# test_module.net
KiCad netlist of a schematic drawn in EAGLE
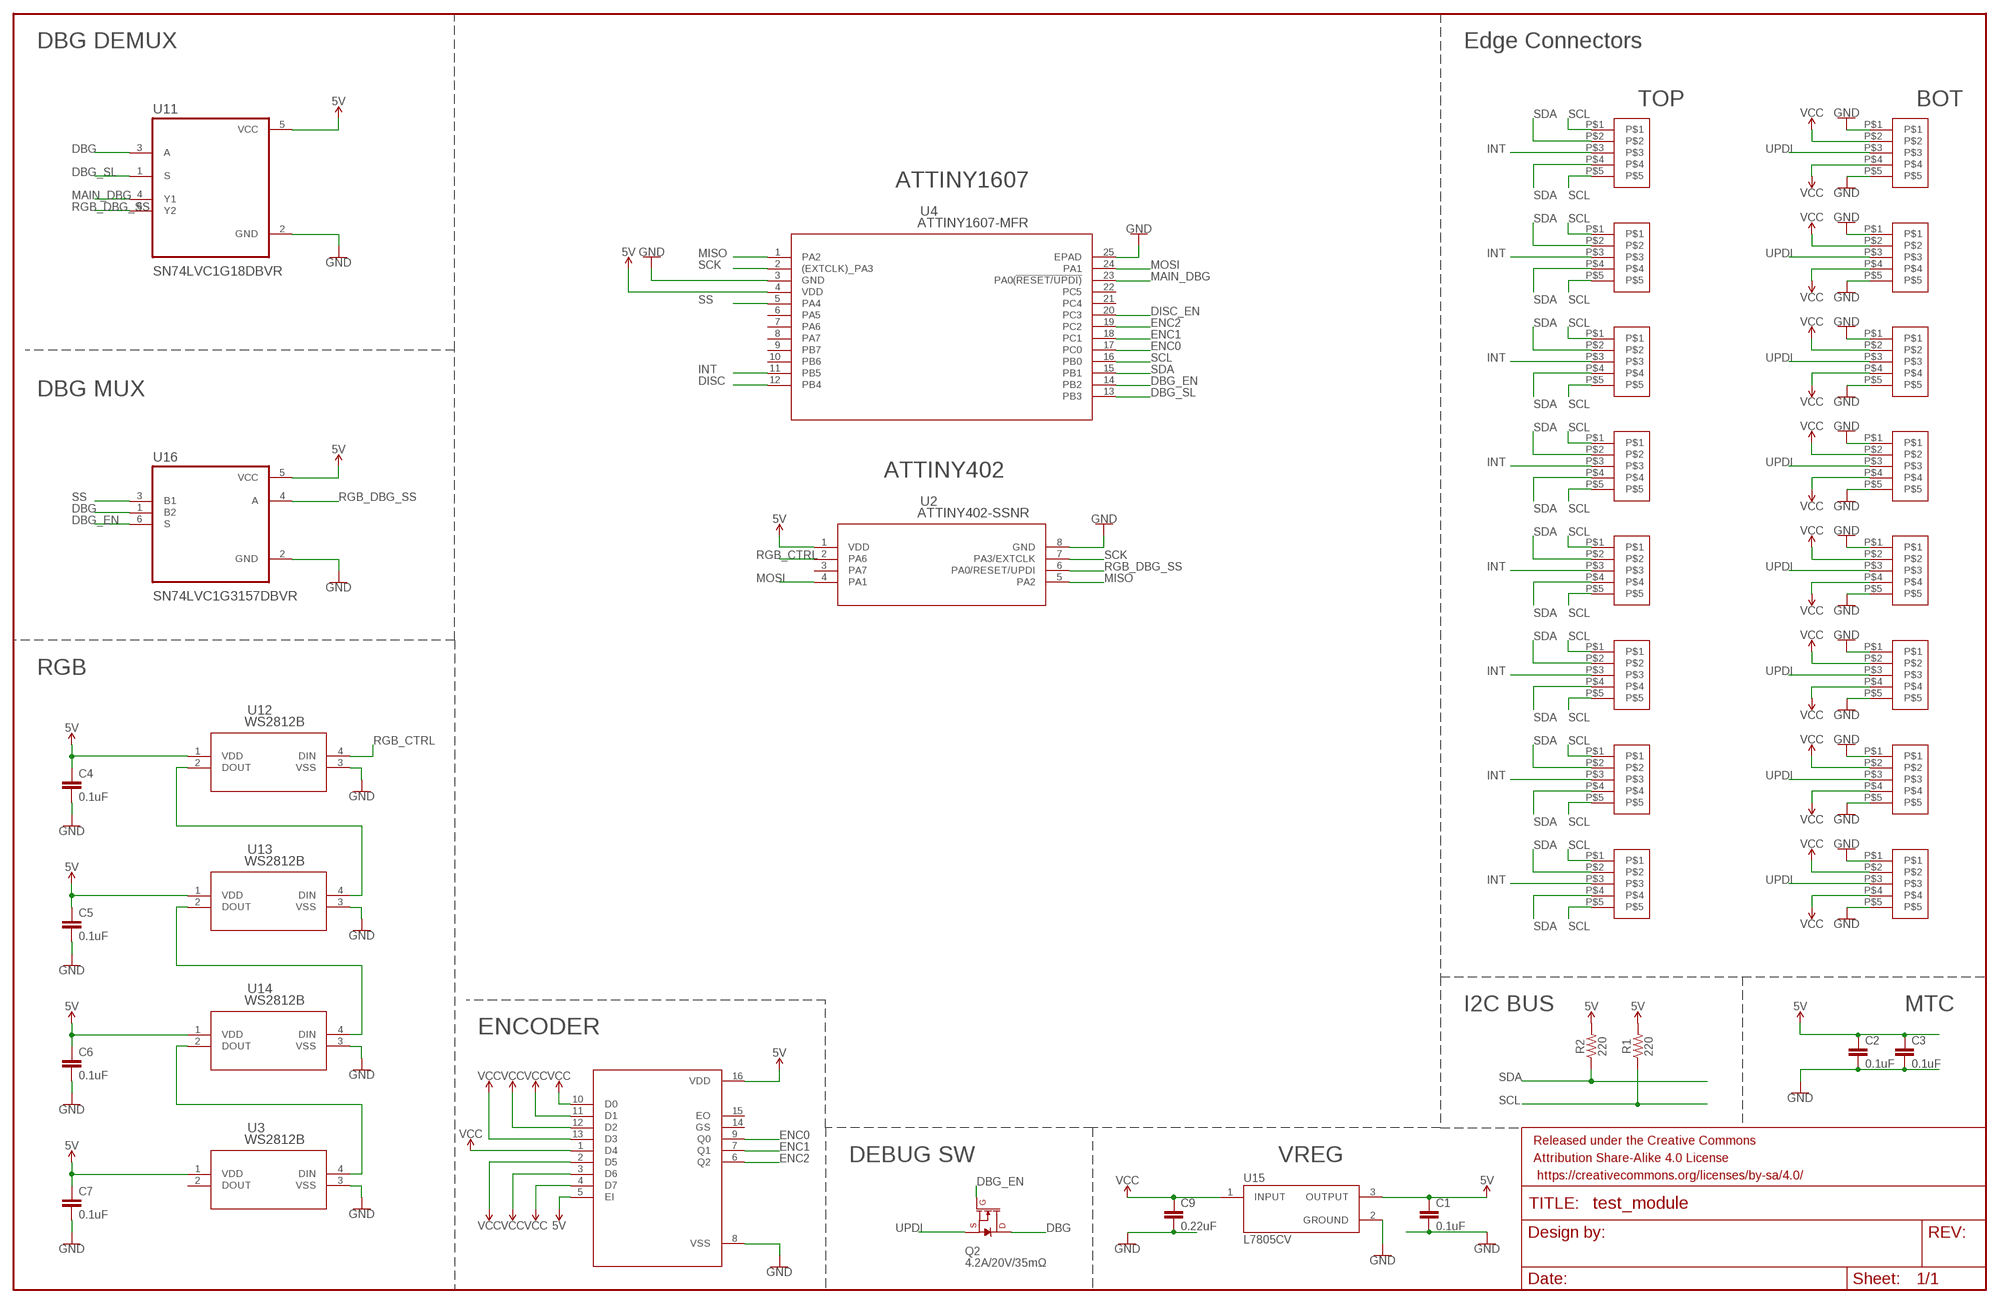
[diagram p0: schematic, sheet 1]

(export (version "E")
  (design (tool "Eeschema 10.0.6"))
  (components
    (comp (ref "C1")
      (value "0.1uF")
      (footprint "eagle-import:0603")
      (libsource (lib "eagle-import") (part "0.1UF-0603-25V-10%-X7R-WE"))
    )
    (comp (ref "C2")
      (value "0.1uF")
      (footprint "eagle-import:0603")
      (libsource (lib "eagle-import") (part "0.1UF-0603-25V-10%-X7R-WE"))
    )
    (comp (ref "C3")
      (value "0.1uF")
      (footprint "eagle-import:0603")
      (libsource (lib "eagle-import") (part "0.1UF-0603-25V-10%-X7R-WE"))
    )
    (comp (ref "C4")
      (value "0.1uF")
      (footprint "eagle-import:0603")
      (libsource (lib "eagle-import") (part "0.1UF-0603-25V-10%-X7R-WE"))
    )
    (comp (ref "C5")
      (value "0.1uF")
      (footprint "eagle-import:0603")
      (libsource (lib "eagle-import") (part "0.1UF-0603-25V-10%-X7R-WE"))
    )
    (comp (ref "C6")
      (value "0.1uF")
      (footprint "eagle-import:0603")
      (libsource (lib "eagle-import") (part "0.1UF-0603-25V-10%-X7R-WE"))
    )
    (comp (ref "C7")
      (value "0.1uF")
      (footprint "eagle-import:0603")
      (libsource (lib "eagle-import") (part "0.1UF-0603-25V-10%-X7R-WE"))
    )
    (comp (ref "C9")
      (value "0.22uF")
      (footprint "eagle-import:1206")
      (libsource (lib "eagle-import") (part "2.2UF-1206-50V-10%"))
    )
    (comp (ref "E1")
      (value "5-PIN-EDGE-CONNECTOR")
      (footprint "eagle-import:5-PIN-EDGE-CONNECTOR")
      (libsource (lib "eagle-import") (part "5-PIN-EDGE-CONNECTOR"))
    )
    (comp (ref "E2")
      (value "5-PIN-EDGE-CONNECTOR")
      (footprint "eagle-import:5-PIN-EDGE-CONNECTOR")
      (libsource (lib "eagle-import") (part "5-PIN-EDGE-CONNECTOR"))
    )
    (comp (ref "E3")
      (value "5-PIN-EDGE-CONNECTOR")
      (footprint "eagle-import:5-PIN-EDGE-CONNECTOR")
      (libsource (lib "eagle-import") (part "5-PIN-EDGE-CONNECTOR"))
    )
    (comp (ref "E4")
      (value "5-PIN-EDGE-CONNECTOR")
      (footprint "eagle-import:5-PIN-EDGE-CONNECTOR")
      (libsource (lib "eagle-import") (part "5-PIN-EDGE-CONNECTOR"))
    )
    (comp (ref "E5")
      (value "5-PIN-EDGE-CONNECTOR")
      (footprint "eagle-import:5-PIN-EDGE-CONNECTOR")
      (libsource (lib "eagle-import") (part "5-PIN-EDGE-CONNECTOR"))
    )
    (comp (ref "E6")
      (value "5-PIN-EDGE-CONNECTOR")
      (footprint "eagle-import:5-PIN-EDGE-CONNECTOR")
      (libsource (lib "eagle-import") (part "5-PIN-EDGE-CONNECTOR"))
    )
    (comp (ref "E7")
      (value "5-PIN-EDGE-CONNECTOR")
      (footprint "eagle-import:5-PIN-EDGE-CONNECTOR")
      (libsource (lib "eagle-import") (part "5-PIN-EDGE-CONNECTOR"))
    )
    (comp (ref "E8")
      (value "5-PIN-EDGE-CONNECTOR")
      (footprint "eagle-import:5-PIN-EDGE-CONNECTOR")
      (libsource (lib "eagle-import") (part "5-PIN-EDGE-CONNECTOR"))
    )
    (comp (ref "E9")
      (value "5-PIN-EDGE-CONNECTOR")
      (footprint "eagle-import:5-PIN-EDGE-CONNECTOR")
      (libsource (lib "eagle-import") (part "5-PIN-EDGE-CONNECTOR"))
    )
    (comp (ref "E10")
      (value "5-PIN-EDGE-CONNECTOR")
      (footprint "eagle-import:5-PIN-EDGE-CONNECTOR")
      (libsource (lib "eagle-import") (part "5-PIN-EDGE-CONNECTOR"))
    )
    (comp (ref "E11")
      (value "5-PIN-EDGE-CONNECTOR")
      (footprint "eagle-import:5-PIN-EDGE-CONNECTOR")
      (libsource (lib "eagle-import") (part "5-PIN-EDGE-CONNECTOR"))
    )
    (comp (ref "E12")
      (value "5-PIN-EDGE-CONNECTOR")
      (footprint "eagle-import:5-PIN-EDGE-CONNECTOR")
      (libsource (lib "eagle-import") (part "5-PIN-EDGE-CONNECTOR"))
    )
    (comp (ref "E13")
      (value "5-PIN-EDGE-CONNECTOR")
      (footprint "eagle-import:5-PIN-EDGE-CONNECTOR")
      (libsource (lib "eagle-import") (part "5-PIN-EDGE-CONNECTOR"))
    )
    (comp (ref "E14")
      (value "5-PIN-EDGE-CONNECTOR")
      (footprint "eagle-import:5-PIN-EDGE-CONNECTOR")
      (libsource (lib "eagle-import") (part "5-PIN-EDGE-CONNECTOR"))
    )
    (comp (ref "E15")
      (value "5-PIN-EDGE-CONNECTOR")
      (footprint "eagle-import:5-PIN-EDGE-CONNECTOR")
      (libsource (lib "eagle-import") (part "5-PIN-EDGE-CONNECTOR"))
    )
    (comp (ref "E16")
      (value "5-PIN-EDGE-CONNECTOR")
      (footprint "eagle-import:5-PIN-EDGE-CONNECTOR")
      (libsource (lib "eagle-import") (part "5-PIN-EDGE-CONNECTOR"))
    )
    (comp (ref "FRAME1")
      (value "FRAME-LEDGER")
      (footprint "eagle-import:CREATIVE_COMMONS")
      (libsource (lib "eagle-import") (part "FRAME-LEDGER"))
    )
    (comp (ref "Q2")
      (value "4.2A/20V/35mΩ")
      (footprint "eagle-import:SOT23-3")
      (libsource (lib "eagle-import") (part "MOSFET-NCH-AO3404A"))
    )
    (comp (ref "R1")
      (value "220")
      (footprint "eagle-import:0603")
      (libsource (lib "eagle-import") (part "220OHM-0603-1/10W-1%"))
    )
    (comp (ref "R2")
      (value "220")
      (footprint "eagle-import:0603")
      (libsource (lib "eagle-import") (part "220OHM-0603-1/10W-1%"))
    )
    (comp (ref "U1")
      (value "CD4532BM")
      (footprint "eagle-import:SOIC127P600X175-16N")
      (libsource (lib "eagle-import") (part "CD4532BM"))
    )
    (comp (ref "U2")
      (value "ATTINY402-SSNR")
      (footprint "eagle-import:SOIC8_4P9X3P9MC_MCH")
      (fields (field (name "COPYRIGHT") "Copyright (C) 2024 Ultra Librarian. All rights reserved."))
      (libsource (lib "eagle-import") (part "ATTINY402-SSNR"))
    )
    (comp (ref "U3")
      (value "WS2812B")
      (footprint "eagle-import:WS2812B_WDS")
      (fields (field (name "COPYRIGHT") "Copyright (C) 2024 Ultra Librarian. All rights reserved."))
      (libsource (lib "eagle-import") (part "WS2812B"))
    )
    (comp (ref "U4")
      (value "ATTINY1607-MFR")
      (footprint "eagle-import:QFN24_4X4_MCH")
      (fields (field (name "COPYRIGHT") "Copyright (C) 2024 Ultra Librarian. All rights reserved."))
      (libsource (lib "eagle-import") (part "ATTINY1607-MFR"))
    )
    (comp (ref "U11")
      (value "SN74LVC1G18DBVR")
      (footprint "eagle-import:SOT95P280X145-6N")
      (fields (field (name "MF") "Texas Instruments"))
      (libsource (lib "eagle-import") (part "SN74LVC1G18DBVR"))
    )
    (comp (ref "U12")
      (value "WS2812B")
      (footprint "eagle-import:WS2812B_WDS")
      (fields (field (name "COPYRIGHT") "Copyright (C) 2024 Ultra Librarian. All rights reserved."))
      (libsource (lib "eagle-import") (part "WS2812B"))
    )
    (comp (ref "U13")
      (value "WS2812B")
      (footprint "eagle-import:WS2812B_WDS")
      (fields (field (name "COPYRIGHT") "Copyright (C) 2024 Ultra Librarian. All rights reserved."))
      (libsource (lib "eagle-import") (part "WS2812B"))
    )
    (comp (ref "U14")
      (value "WS2812B")
      (footprint "eagle-import:WS2812B_WDS")
      (fields (field (name "COPYRIGHT") "Copyright (C) 2024 Ultra Librarian. All rights reserved."))
      (libsource (lib "eagle-import") (part "WS2812B"))
    )
    (comp (ref "U15")
      (value "L7805CV")
      (footprint "eagle-import:TO255P1040X460X1968-3")
      (fields (field (name "MF") "STMicroelectronics") (field (name "MP") "L7805CV-"))
      (libsource (lib "eagle-import") (part "L7805CV"))
    )
    (comp (ref "U16")
      (value "SN74LVC1G3157DBVR")
      (footprint "eagle-import:SOT95P280X145-6N")
      (fields (field (name "MF") "Texas Instruments"))
      (libsource (lib "eagle-import") (part "SN74LVC1G3157DBVR"))
    )
  )
  (nets
    (net (code "1") (name "/DBG") (class "Default")
      (node (ref "Q2") (pin "3") (pinfunction "D_3") (pintype "bidirectional"))
      (node (ref "U11") (pin "3") (pinfunction "A_3") (pintype "bidirectional"))
      (node (ref "U16") (pin "1") (pinfunction "B2_1") (pintype "input"))
    )
    (net (code "2") (name "/DBG_EN") (class "Default")
      (node (ref "Q2") (pin "1") (pinfunction "G_1") (pintype "bidirectional"))
      (node (ref "U16") (pin "6") (pinfunction "S_6") (pintype "input"))
      (node (ref "U4") (pin "14") (pinfunction "PB2_14") (pintype "bidirectional"))
    )
    (net (code "3") (name "/DBG_SL") (class "Default")
      (node (ref "U11") (pin "1") (pinfunction "S_1") (pintype "bidirectional"))
      (node (ref "U4") (pin "13") (pinfunction "PB3_13") (pintype "bidirectional"))
    )
    (net (code "4") (name "/DISC") (class "Default")
      (node (ref "U4") (pin "12") (pinfunction "PB4_12") (pintype "bidirectional"))
    )
    (net (code "5") (name "/DISC_EN") (class "Default")
      (node (ref "U4") (pin "20") (pinfunction "PC3_20") (pintype "bidirectional"))
    )
    (net (code "6") (name "/ENC0") (class "Default")
      (node (ref "U1") (pin "9") (pinfunction "Q0_9") (pintype "bidirectional"))
      (node (ref "U4") (pin "17") (pinfunction "PC0_17") (pintype "bidirectional"))
    )
    (net (code "7") (name "/ENC1") (class "Default")
      (node (ref "U1") (pin "7") (pinfunction "Q1_7") (pintype "bidirectional"))
      (node (ref "U4") (pin "18") (pinfunction "PC1_18") (pintype "bidirectional"))
    )
    (net (code "8") (name "/ENC2") (class "Default")
      (node (ref "U1") (pin "6") (pinfunction "Q2_6") (pintype "bidirectional"))
      (node (ref "U4") (pin "19") (pinfunction "PC2_19") (pintype "bidirectional"))
    )
    (net (code "9") (name "/INT") (class "Default")
      (node (ref "E1") (pin "P$3") (pinfunction "P$3_P$3") (pintype "bidirectional"))
      (node (ref "E13") (pin "P$3") (pinfunction "P$3_P$3") (pintype "bidirectional"))
      (node (ref "E14") (pin "P$3") (pinfunction "P$3_P$3") (pintype "bidirectional"))
      (node (ref "E15") (pin "P$3") (pinfunction "P$3_P$3") (pintype "bidirectional"))
      (node (ref "E16") (pin "P$3") (pinfunction "P$3_P$3") (pintype "bidirectional"))
      (node (ref "E2") (pin "P$3") (pinfunction "P$3_P$3") (pintype "bidirectional"))
      (node (ref "E3") (pin "P$3") (pinfunction "P$3_P$3") (pintype "bidirectional"))
      (node (ref "E4") (pin "P$3") (pinfunction "P$3_P$3") (pintype "bidirectional"))
      (node (ref "U4") (pin "11") (pinfunction "PB5_11") (pintype "bidirectional"))
    )
    (net (code "10") (name "/MAIN_DBG") (class "Default")
      (node (ref "U11") (pin "4") (pinfunction "Y1_4") (pintype "bidirectional"))
      (node (ref "U4") (pin "23") (pinfunction "PA0(~{RESET/UPDI})_23") (pintype "bidirectional"))
    )
    (net (code "11") (name "/MISO") (class "Default")
      (node (ref "U2") (pin "5") (pinfunction "PA2_5") (pintype "bidirectional"))
      (node (ref "U4") (pin "1") (pinfunction "PA2_1") (pintype "bidirectional"))
    )
    (net (code "12") (name "/MOSI") (class "Default")
      (node (ref "U2") (pin "4") (pinfunction "PA1_4") (pintype "bidirectional"))
      (node (ref "U4") (pin "24") (pinfunction "PA1_24") (pintype "bidirectional"))
    )
    (net (code "13") (name "/RGB_CTRL") (class "Default")
      (node (ref "U12") (pin "4") (pinfunction "DIN_4") (pintype "input"))
      (node (ref "U2") (pin "2") (pinfunction "PA6_2") (pintype "bidirectional"))
    )
    (net (code "14") (name "/RGB_DBG_SS") (class "Default")
      (node (ref "U11") (pin "6") (pinfunction "Y2_6") (pintype "bidirectional"))
      (node (ref "U16") (pin "4") (pinfunction "A_4") (pintype "output"))
      (node (ref "U2") (pin "6") (pinfunction "PA0/RESET/UPDI_6") (pintype "bidirectional"))
    )
    (net (code "15") (name "/SCK") (class "Default")
      (node (ref "U2") (pin "7") (pinfunction "PA3/EXTCLK_7") (pintype "bidirectional"))
      (node (ref "U4") (pin "2") (pinfunction "(EXTCLK)_PA3_2") (pintype "passive"))
    )
    (net (code "16") (name "/SCL") (class "Default")
      (node (ref "E1") (pin "P$1") (pinfunction "P$1_P$1") (pintype "bidirectional"))
      (node (ref "E1") (pin "P$5") (pinfunction "P$5_P$5") (pintype "bidirectional"))
      (node (ref "E13") (pin "P$1") (pinfunction "P$1_P$1") (pintype "bidirectional"))
      (node (ref "E13") (pin "P$5") (pinfunction "P$5_P$5") (pintype "bidirectional"))
      (node (ref "E14") (pin "P$1") (pinfunction "P$1_P$1") (pintype "bidirectional"))
      (node (ref "E14") (pin "P$5") (pinfunction "P$5_P$5") (pintype "bidirectional"))
      (node (ref "E15") (pin "P$1") (pinfunction "P$1_P$1") (pintype "bidirectional"))
      (node (ref "E15") (pin "P$5") (pinfunction "P$5_P$5") (pintype "bidirectional"))
      (node (ref "E16") (pin "P$1") (pinfunction "P$1_P$1") (pintype "bidirectional"))
      (node (ref "E16") (pin "P$5") (pinfunction "P$5_P$5") (pintype "bidirectional"))
      (node (ref "E2") (pin "P$1") (pinfunction "P$1_P$1") (pintype "bidirectional"))
      (node (ref "E2") (pin "P$5") (pinfunction "P$5_P$5") (pintype "bidirectional"))
      (node (ref "E3") (pin "P$1") (pinfunction "P$1_P$1") (pintype "bidirectional"))
      (node (ref "E3") (pin "P$5") (pinfunction "P$5_P$5") (pintype "bidirectional"))
      (node (ref "E4") (pin "P$1") (pinfunction "P$1_P$1") (pintype "bidirectional"))
      (node (ref "E4") (pin "P$5") (pinfunction "P$5_P$5") (pintype "bidirectional"))
      (node (ref "R1") (pin "1") (pinfunction "1_1") (pintype "passive"))
      (node (ref "U4") (pin "16") (pinfunction "PB0_16") (pintype "bidirectional"))
    )
    (net (code "17") (name "/SDA") (class "Default")
      (node (ref "E1") (pin "P$2") (pinfunction "P$2_P$2") (pintype "bidirectional"))
      (node (ref "E1") (pin "P$4") (pinfunction "P$4_P$4") (pintype "bidirectional"))
      (node (ref "E13") (pin "P$2") (pinfunction "P$2_P$2") (pintype "bidirectional"))
      (node (ref "E13") (pin "P$4") (pinfunction "P$4_P$4") (pintype "bidirectional"))
      (node (ref "E14") (pin "P$2") (pinfunction "P$2_P$2") (pintype "bidirectional"))
      (node (ref "E14") (pin "P$4") (pinfunction "P$4_P$4") (pintype "bidirectional"))
      (node (ref "E15") (pin "P$2") (pinfunction "P$2_P$2") (pintype "bidirectional"))
      (node (ref "E15") (pin "P$4") (pinfunction "P$4_P$4") (pintype "bidirectional"))
      (node (ref "E16") (pin "P$2") (pinfunction "P$2_P$2") (pintype "bidirectional"))
      (node (ref "E16") (pin "P$4") (pinfunction "P$4_P$4") (pintype "bidirectional"))
      (node (ref "E2") (pin "P$2") (pinfunction "P$2_P$2") (pintype "bidirectional"))
      (node (ref "E2") (pin "P$4") (pinfunction "P$4_P$4") (pintype "bidirectional"))
      (node (ref "E3") (pin "P$2") (pinfunction "P$2_P$2") (pintype "bidirectional"))
      (node (ref "E3") (pin "P$4") (pinfunction "P$4_P$4") (pintype "bidirectional"))
      (node (ref "E4") (pin "P$2") (pinfunction "P$2_P$2") (pintype "bidirectional"))
      (node (ref "E4") (pin "P$4") (pinfunction "P$4_P$4") (pintype "bidirectional"))
      (node (ref "R2") (pin "1") (pinfunction "1_1") (pintype "passive"))
      (node (ref "U4") (pin "15") (pinfunction "PB1_15") (pintype "bidirectional"))
    )
    (net (code "18") (name "/SS") (class "Default")
      (node (ref "U16") (pin "3") (pinfunction "B1_3") (pintype "input"))
      (node (ref "U4") (pin "5") (pinfunction "PA4_5") (pintype "bidirectional"))
    )
    (net (code "19") (name "/UPDI") (class "Default")
      (node (ref "E10") (pin "P$3") (pinfunction "P$3_P$3") (pintype "bidirectional"))
      (node (ref "E11") (pin "P$3") (pinfunction "P$3_P$3") (pintype "bidirectional"))
      (node (ref "E12") (pin "P$3") (pinfunction "P$3_P$3") (pintype "bidirectional"))
      (node (ref "E5") (pin "P$3") (pinfunction "P$3_P$3") (pintype "bidirectional"))
      (node (ref "E6") (pin "P$3") (pinfunction "P$3_P$3") (pintype "bidirectional"))
      (node (ref "E7") (pin "P$3") (pinfunction "P$3_P$3") (pintype "bidirectional"))
      (node (ref "E8") (pin "P$3") (pinfunction "P$3_P$3") (pintype "bidirectional"))
      (node (ref "E9") (pin "P$3") (pinfunction "P$3_P$3") (pintype "bidirectional"))
      (node (ref "Q2") (pin "2") (pinfunction "S_2") (pintype "bidirectional"))
    )
    (net (code "20") (name "5V") (class "Default")
      (node (ref "C1") (pin "1") (pinfunction "1_1") (pintype "passive"))
      (node (ref "C2") (pin "1") (pinfunction "1_1") (pintype "passive"))
      (node (ref "C3") (pin "1") (pinfunction "1_1") (pintype "passive"))
      (node (ref "C4") (pin "1") (pinfunction "1_1") (pintype "passive"))
      (node (ref "C5") (pin "1") (pinfunction "1_1") (pintype "passive"))
      (node (ref "C6") (pin "1") (pinfunction "1_1") (pintype "passive"))
      (node (ref "C7") (pin "1") (pinfunction "1_1") (pintype "passive"))
      (node (ref "R1") (pin "2") (pinfunction "2_2") (pintype "passive"))
      (node (ref "R2") (pin "2") (pinfunction "2_2") (pintype "passive"))
      (node (ref "U1") (pin "16") (pinfunction "VDD_16") (pintype "bidirectional"))
      (node (ref "U1") (pin "5") (pinfunction "EI_5") (pintype "bidirectional"))
      (node (ref "U11") (pin "5") (pinfunction "VCC_5") (pintype "power_in"))
      (node (ref "U12") (pin "1") (pinfunction "VDD_1") (pintype "power_in"))
      (node (ref "U13") (pin "1") (pinfunction "VDD_1") (pintype "power_in"))
      (node (ref "U14") (pin "1") (pinfunction "VDD_1") (pintype "power_in"))
      (node (ref "U15") (pin "3") (pinfunction "OUTPUT_3") (pintype "output"))
      (node (ref "U16") (pin "5") (pinfunction "VCC_5") (pintype "power_in"))
      (node (ref "U2") (pin "1") (pinfunction "VDD_1") (pintype "power_in"))
      (node (ref "U3") (pin "1") (pinfunction "VDD_1") (pintype "power_in"))
      (node (ref "U4") (pin "4") (pinfunction "VDD_4") (pintype "power_in"))
    )
    (net (code "21") (name "GND") (class "Default")
      (node (ref "C1") (pin "2") (pinfunction "2_2") (pintype "passive"))
      (node (ref "C2") (pin "2") (pinfunction "2_2") (pintype "passive"))
      (node (ref "C3") (pin "2") (pinfunction "2_2") (pintype "passive"))
      (node (ref "C4") (pin "2") (pinfunction "2_2") (pintype "passive"))
      (node (ref "C5") (pin "2") (pinfunction "2_2") (pintype "passive"))
      (node (ref "C6") (pin "2") (pinfunction "2_2") (pintype "passive"))
      (node (ref "C7") (pin "2") (pinfunction "2_2") (pintype "passive"))
      (node (ref "C9") (pin "2") (pinfunction "2_2") (pintype "passive"))
      (node (ref "E10") (pin "P$1") (pinfunction "P$1_P$1") (pintype "bidirectional"))
      (node (ref "E10") (pin "P$5") (pinfunction "P$5_P$5") (pintype "bidirectional"))
      (node (ref "E11") (pin "P$1") (pinfunction "P$1_P$1") (pintype "bidirectional"))
      (node (ref "E11") (pin "P$5") (pinfunction "P$5_P$5") (pintype "bidirectional"))
      (node (ref "E12") (pin "P$1") (pinfunction "P$1_P$1") (pintype "bidirectional"))
      (node (ref "E12") (pin "P$5") (pinfunction "P$5_P$5") (pintype "bidirectional"))
      (node (ref "E5") (pin "P$1") (pinfunction "P$1_P$1") (pintype "bidirectional"))
      (node (ref "E5") (pin "P$5") (pinfunction "P$5_P$5") (pintype "bidirectional"))
      (node (ref "E6") (pin "P$1") (pinfunction "P$1_P$1") (pintype "bidirectional"))
      (node (ref "E6") (pin "P$5") (pinfunction "P$5_P$5") (pintype "bidirectional"))
      (node (ref "E7") (pin "P$1") (pinfunction "P$1_P$1") (pintype "bidirectional"))
      (node (ref "E7") (pin "P$5") (pinfunction "P$5_P$5") (pintype "bidirectional"))
      (node (ref "E8") (pin "P$1") (pinfunction "P$1_P$1") (pintype "bidirectional"))
      (node (ref "E8") (pin "P$5") (pinfunction "P$5_P$5") (pintype "bidirectional"))
      (node (ref "E9") (pin "P$1") (pinfunction "P$1_P$1") (pintype "bidirectional"))
      (node (ref "E9") (pin "P$5") (pinfunction "P$5_P$5") (pintype "bidirectional"))
      (node (ref "U1") (pin "8") (pinfunction "VSS_8") (pintype "bidirectional"))
      (node (ref "U11") (pin "2") (pinfunction "GND_2") (pintype "power_in"))
      (node (ref "U12") (pin "3") (pinfunction "VSS_3") (pintype "passive"))
      (node (ref "U13") (pin "3") (pinfunction "VSS_3") (pintype "passive"))
      (node (ref "U14") (pin "3") (pinfunction "VSS_3") (pintype "passive"))
      (node (ref "U15") (pin "2") (pinfunction "GROUND_2") (pintype "power_in"))
      (node (ref "U16") (pin "2") (pinfunction "GND_2") (pintype "power_in"))
      (node (ref "U2") (pin "8") (pinfunction "GND_8") (pintype "passive"))
      (node (ref "U3") (pin "3") (pinfunction "VSS_3") (pintype "passive"))
      (node (ref "U4") (pin "25") (pinfunction "EPAD_25") (pintype "passive"))
      (node (ref "U4") (pin "3") (pinfunction "GND_3") (pintype "passive"))
    )
    (net (code "22") (name "Net-(U12-DOUT)") (class "Default")
      (node (ref "U12") (pin "2") (pinfunction "DOUT_2") (pintype "output"))
      (node (ref "U13") (pin "4") (pinfunction "DIN_4") (pintype "input"))
    )
    (net (code "23") (name "Net-(U13-DOUT)") (class "Default")
      (node (ref "U13") (pin "2") (pinfunction "DOUT_2") (pintype "output"))
      (node (ref "U14") (pin "4") (pinfunction "DIN_4") (pintype "input"))
    )
    (net (code "24") (name "Net-(U14-DOUT)") (class "Default")
      (node (ref "U14") (pin "2") (pinfunction "DOUT_2") (pintype "output"))
      (node (ref "U3") (pin "4") (pinfunction "DIN_4") (pintype "input"))
    )
    (net (code "25") (name "VCC") (class "Default")
      (node (ref "C9") (pin "1") (pinfunction "1_1") (pintype "passive"))
      (node (ref "E10") (pin "P$2") (pinfunction "P$2_P$2") (pintype "bidirectional"))
      (node (ref "E10") (pin "P$4") (pinfunction "P$4_P$4") (pintype "bidirectional"))
      (node (ref "E11") (pin "P$2") (pinfunction "P$2_P$2") (pintype "bidirectional"))
      (node (ref "E11") (pin "P$4") (pinfunction "P$4_P$4") (pintype "bidirectional"))
      (node (ref "E12") (pin "P$2") (pinfunction "P$2_P$2") (pintype "bidirectional"))
      (node (ref "E12") (pin "P$4") (pinfunction "P$4_P$4") (pintype "bidirectional"))
      (node (ref "E5") (pin "P$2") (pinfunction "P$2_P$2") (pintype "bidirectional"))
      (node (ref "E5") (pin "P$4") (pinfunction "P$4_P$4") (pintype "bidirectional"))
      (node (ref "E6") (pin "P$2") (pinfunction "P$2_P$2") (pintype "bidirectional"))
      (node (ref "E6") (pin "P$4") (pinfunction "P$4_P$4") (pintype "bidirectional"))
      (node (ref "E7") (pin "P$2") (pinfunction "P$2_P$2") (pintype "bidirectional"))
      (node (ref "E7") (pin "P$4") (pinfunction "P$4_P$4") (pintype "bidirectional"))
      (node (ref "E8") (pin "P$2") (pinfunction "P$2_P$2") (pintype "bidirectional"))
      (node (ref "E8") (pin "P$4") (pinfunction "P$4_P$4") (pintype "bidirectional"))
      (node (ref "E9") (pin "P$2") (pinfunction "P$2_P$2") (pintype "bidirectional"))
      (node (ref "E9") (pin "P$4") (pinfunction "P$4_P$4") (pintype "bidirectional"))
      (node (ref "U1") (pin "1") (pinfunction "D4_1") (pintype "bidirectional"))
      (node (ref "U1") (pin "10") (pinfunction "D0_10") (pintype "bidirectional"))
      (node (ref "U1") (pin "11") (pinfunction "D1_11") (pintype "bidirectional"))
      (node (ref "U1") (pin "12") (pinfunction "D2_12") (pintype "bidirectional"))
      (node (ref "U1") (pin "13") (pinfunction "D3_13") (pintype "bidirectional"))
      (node (ref "U1") (pin "2") (pinfunction "D5_2") (pintype "bidirectional"))
      (node (ref "U1") (pin "3") (pinfunction "D6_3") (pintype "bidirectional"))
      (node (ref "U1") (pin "4") (pinfunction "D7_4") (pintype "bidirectional"))
      (node (ref "U15") (pin "1") (pinfunction "INPUT_1") (pintype "input"))
    )
    (net (code "26") (name "unconnected-(U1-EO-Pad15)") (class "Default")
      (node (ref "U1") (pin "15") (pinfunction "EO_15") (pintype "bidirectional"))
    )
    (net (code "27") (name "unconnected-(U1-GS-Pad14)") (class "Default")
      (node (ref "U1") (pin "14") (pinfunction "GS_14") (pintype "bidirectional"))
    )
    (net (code "28") (name "unconnected-(U2-PA7-Pad3)") (class "Default")
      (node (ref "U2") (pin "3") (pinfunction "PA7_3") (pintype "bidirectional"))
    )
    (net (code "29") (name "unconnected-(U3-DOUT-Pad2)") (class "Default")
      (node (ref "U3") (pin "2") (pinfunction "DOUT_2") (pintype "output"))
    )
    (net (code "30") (name "unconnected-(U4-PA5-Pad6)") (class "Default")
      (node (ref "U4") (pin "6") (pinfunction "PA5_6") (pintype "bidirectional"))
    )
    (net (code "31") (name "unconnected-(U4-PA6-Pad7)") (class "Default")
      (node (ref "U4") (pin "7") (pinfunction "PA6_7") (pintype "bidirectional"))
    )
    (net (code "32") (name "unconnected-(U4-PA7-Pad8)") (class "Default")
      (node (ref "U4") (pin "8") (pinfunction "PA7_8") (pintype "bidirectional"))
    )
    (net (code "33") (name "unconnected-(U4-PB6-Pad10)") (class "Default")
      (node (ref "U4") (pin "10") (pinfunction "PB6_10") (pintype "bidirectional"))
    )
    (net (code "34") (name "unconnected-(U4-PB7-Pad9)") (class "Default")
      (node (ref "U4") (pin "9") (pinfunction "PB7_9") (pintype "bidirectional"))
    )
    (net (code "35") (name "unconnected-(U4-PC4-Pad21)") (class "Default")
      (node (ref "U4") (pin "21") (pinfunction "PC4_21") (pintype "bidirectional"))
    )
    (net (code "36") (name "unconnected-(U4-PC5-Pad22)") (class "Default")
      (node (ref "U4") (pin "22") (pinfunction "PC5_22") (pintype "bidirectional"))
    )
  )
)
